# Ex_Controller.net
KiCad netlist of a schematic drawn in EAGLE
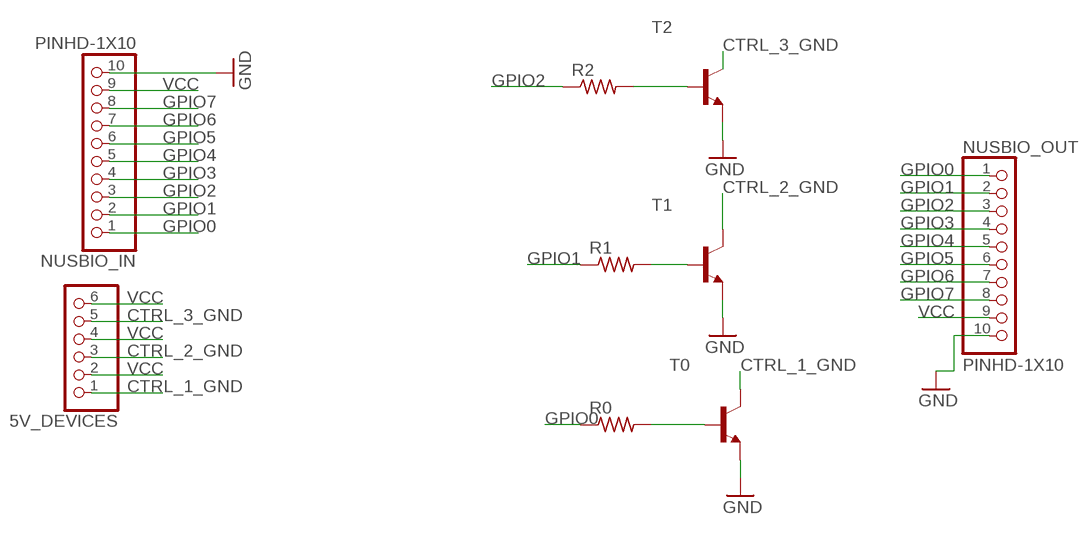
[diagram p0: schematic, sheet 1]

(export (version "E")
  (design (tool "Eeschema 10.0.6"))
  (components
    (comp (ref "5V_DEVICES")
      (value "PINHD-1X6")
      (footprint "eagle-import:1X06")
      (libsource (lib "eagle-import") (part "PINHD-1X6"))
    )
    (comp (ref "NUSBIO_IN")
      (value "PINHD-1X10")
      (footprint "eagle-import:1X10-BIG")
      (libsource (lib "eagle-import") (part "PINHD-1X10"))
    )
    (comp (ref "NUSBIO_OUT")
      (value "PINHD-1X10")
      (footprint "eagle-import:1X10-BIG")
      (libsource (lib "eagle-import") (part "PINHD-1X10"))
    )
    (comp (ref "R0")
      (value "R-US_R0805")
      (footprint "eagle-import:R0805")
      (libsource (lib "eagle-import") (part "R-US_R0805"))
    )
    (comp (ref "R1")
      (value "R-US_R0805")
      (footprint "eagle-import:R0805")
      (libsource (lib "eagle-import") (part "R-US_R0805"))
    )
    (comp (ref "R2")
      (value "R-US_R0805")
      (footprint "eagle-import:R0805")
      (libsource (lib "eagle-import") (part "R-US_R0805"))
    )
    (comp (ref "T0")
      (value "MMBT3904LT1-NPN-SOT23-BEC")
      (footprint "eagle-import:SOT23-BEC")
      (libsource (lib "eagle-import") (part "-NPN-SOT23-BECMMBT3904LT1"))
    )
    (comp (ref "T1")
      (value "MMBT3904LT1-NPN-SOT23-BEC")
      (footprint "eagle-import:SOT23-BEC")
      (libsource (lib "eagle-import") (part "-NPN-SOT23-BECMMBT3904LT1"))
    )
    (comp (ref "T2")
      (value "MMBT3904LT1-NPN-SOT23-BEC")
      (footprint "eagle-import:SOT23-BEC")
      (libsource (lib "eagle-import") (part "-NPN-SOT23-BECMMBT3904LT1"))
    )
  )
  (nets
    (net (code "1") (name "/CTRL_1_GND") (class "Default")
      (node (ref "5V_DEVICES") (pin "1") (pinfunction "1_1") (pintype "passive"))
      (node (ref "T0") (pin "C") (pinfunction "C_C") (pintype "passive"))
    )
    (net (code "2") (name "/CTRL_2_GND") (class "Default")
      (node (ref "5V_DEVICES") (pin "3") (pinfunction "3_3") (pintype "passive"))
      (node (ref "T1") (pin "C") (pinfunction "C_C") (pintype "passive"))
    )
    (net (code "3") (name "/CTRL_3_GND") (class "Default")
      (node (ref "5V_DEVICES") (pin "5") (pinfunction "5_5") (pintype "passive"))
      (node (ref "T2") (pin "C") (pinfunction "C_C") (pintype "passive"))
    )
    (net (code "4") (name "/GPIO0") (class "Default")
      (node (ref "NUSBIO_IN") (pin "1") (pinfunction "1_1") (pintype "passive"))
      (node (ref "NUSBIO_OUT") (pin "1") (pinfunction "1_1") (pintype "passive"))
      (node (ref "R0") (pin "1") (pinfunction "1_1") (pintype "passive"))
    )
    (net (code "5") (name "/GPIO1") (class "Default")
      (node (ref "NUSBIO_IN") (pin "2") (pinfunction "2_2") (pintype "passive"))
      (node (ref "NUSBIO_OUT") (pin "2") (pinfunction "2_2") (pintype "passive"))
      (node (ref "R1") (pin "1") (pinfunction "1_1") (pintype "passive"))
    )
    (net (code "6") (name "/GPIO2") (class "Default")
      (node (ref "NUSBIO_IN") (pin "3") (pinfunction "3_3") (pintype "passive"))
      (node (ref "NUSBIO_OUT") (pin "3") (pinfunction "3_3") (pintype "passive"))
      (node (ref "R2") (pin "1") (pinfunction "1_1") (pintype "passive"))
    )
    (net (code "7") (name "/GPIO3") (class "Default")
      (node (ref "NUSBIO_IN") (pin "4") (pinfunction "4_4") (pintype "passive"))
      (node (ref "NUSBIO_OUT") (pin "4") (pinfunction "4_4") (pintype "passive"))
    )
    (net (code "8") (name "/GPIO4") (class "Default")
      (node (ref "NUSBIO_IN") (pin "5") (pinfunction "5_5") (pintype "passive"))
      (node (ref "NUSBIO_OUT") (pin "5") (pinfunction "5_5") (pintype "passive"))
    )
    (net (code "9") (name "/GPIO5") (class "Default")
      (node (ref "NUSBIO_IN") (pin "6") (pinfunction "6_6") (pintype "passive"))
      (node (ref "NUSBIO_OUT") (pin "6") (pinfunction "6_6") (pintype "passive"))
    )
    (net (code "10") (name "/GPIO6") (class "Default")
      (node (ref "NUSBIO_IN") (pin "7") (pinfunction "7_7") (pintype "passive"))
      (node (ref "NUSBIO_OUT") (pin "7") (pinfunction "7_7") (pintype "passive"))
    )
    (net (code "11") (name "/GPIO7") (class "Default")
      (node (ref "NUSBIO_IN") (pin "8") (pinfunction "8_8") (pintype "passive"))
      (node (ref "NUSBIO_OUT") (pin "8") (pinfunction "8_8") (pintype "passive"))
    )
    (net (code "12") (name "/VCC") (class "Default")
      (node (ref "5V_DEVICES") (pin "2") (pinfunction "2_2") (pintype "passive"))
      (node (ref "5V_DEVICES") (pin "4") (pinfunction "4_4") (pintype "passive"))
      (node (ref "5V_DEVICES") (pin "6") (pinfunction "6_6") (pintype "passive"))
      (node (ref "NUSBIO_IN") (pin "9") (pinfunction "9_9") (pintype "passive"))
      (node (ref "NUSBIO_OUT") (pin "9") (pinfunction "9_9") (pintype "passive"))
    )
    (net (code "13") (name "GND") (class "Default")
      (node (ref "NUSBIO_IN") (pin "10") (pinfunction "10_10") (pintype "passive"))
      (node (ref "NUSBIO_OUT") (pin "10") (pinfunction "10_10") (pintype "passive"))
      (node (ref "T0") (pin "E") (pinfunction "E_E") (pintype "passive"))
      (node (ref "T1") (pin "E") (pinfunction "E_E") (pintype "passive"))
      (node (ref "T2") (pin "E") (pinfunction "E_E") (pintype "passive"))
    )
    (net (code "14") (name "Net-(R0-Pad2)") (class "Default")
      (node (ref "R0") (pin "2") (pinfunction "2_2") (pintype "passive"))
      (node (ref "T0") (pin "B") (pinfunction "B_B") (pintype "passive"))
    )
    (net (code "15") (name "Net-(R1-Pad2)") (class "Default")
      (node (ref "R1") (pin "2") (pinfunction "2_2") (pintype "passive"))
      (node (ref "T1") (pin "B") (pinfunction "B_B") (pintype "passive"))
    )
    (net (code "16") (name "Net-(R2-Pad2)") (class "Default")
      (node (ref "R2") (pin "2") (pinfunction "2_2") (pintype "passive"))
      (node (ref "T2") (pin "B") (pinfunction "B_B") (pintype "passive"))
    )
  )
)
